# logger_v1.net
KiCad netlist of a schematic drawn in EAGLE
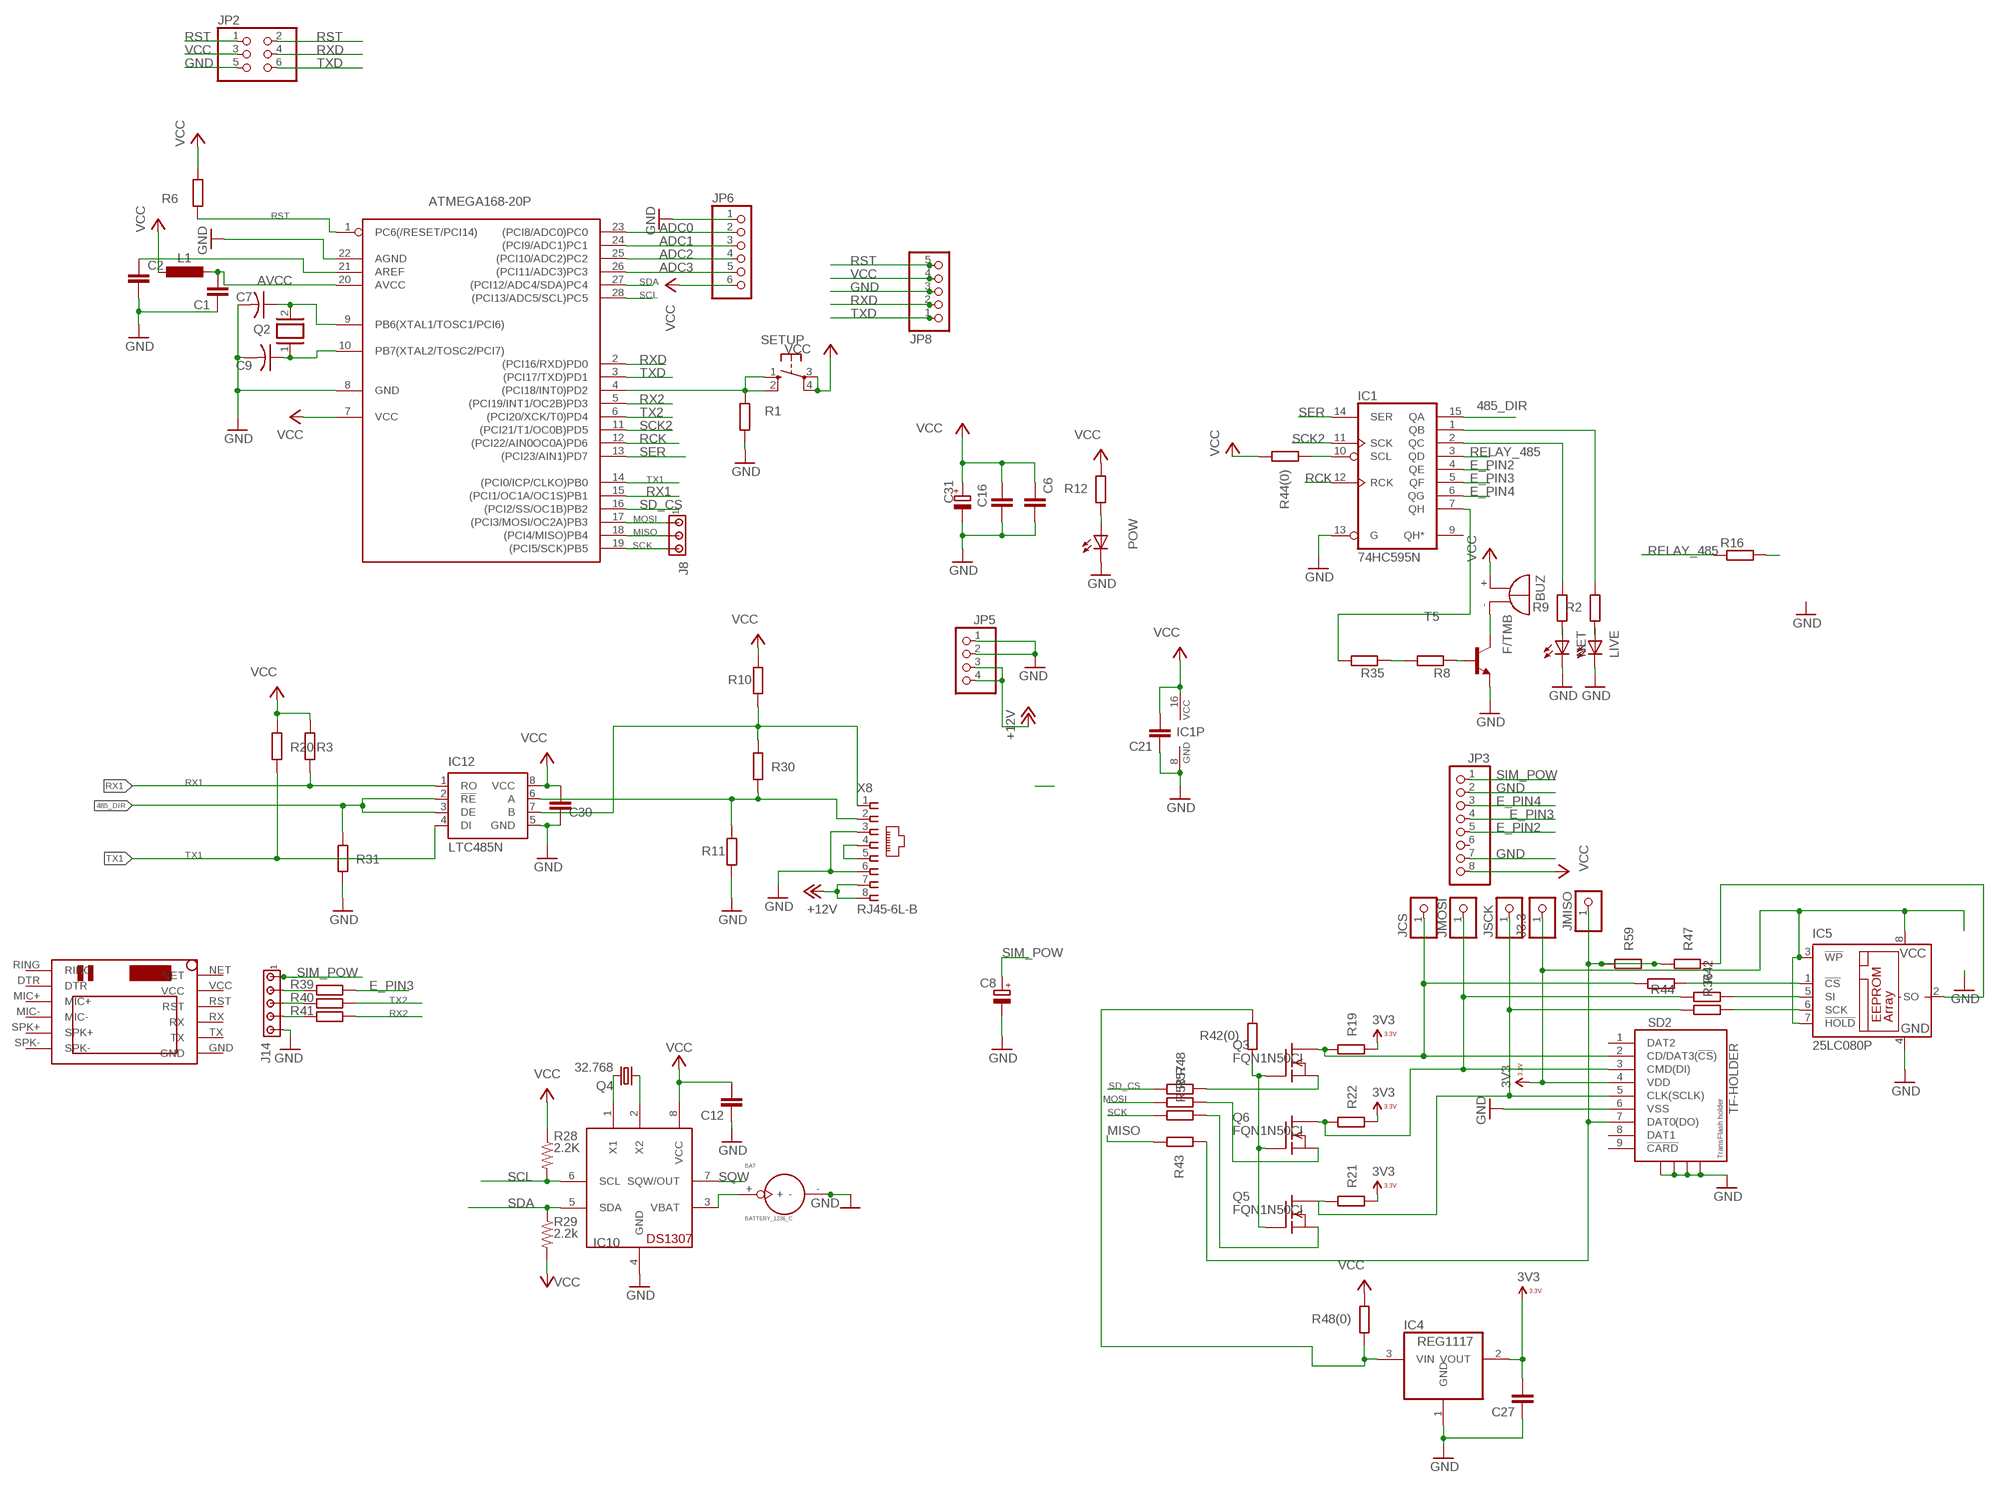
[diagram p0: schematic, sheet 1]
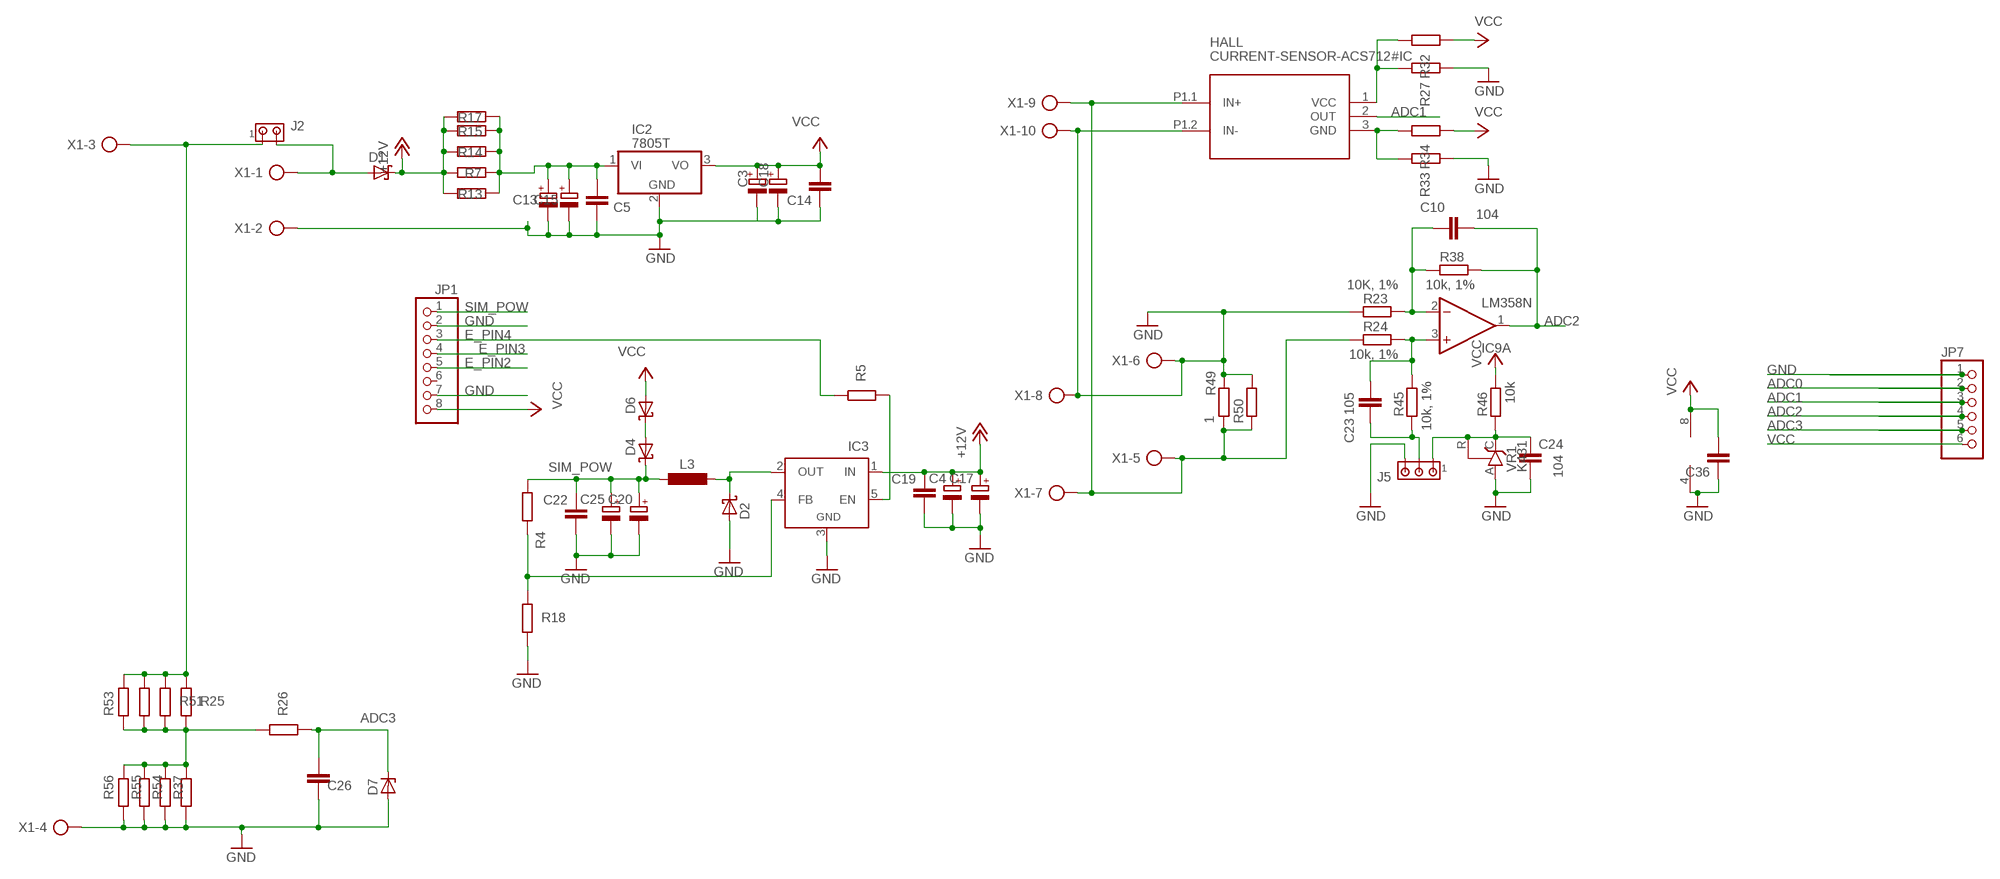
[diagram p1: schematic, sheet 2]

(export (version "E")
  (design (tool "Eeschema 10.0.6"))
  (components
    (comp (ref "C3")
      (value "CPOL-EUTT2D6")
      (footprint "eagle-import:TT2D6")
      (libsource (lib "eagle-import") (part "CPOL-EUTT2D6"))
    )
    (comp (ref "C4")
      (value "CPOL-EUE2.5-6")
      (footprint "eagle-import:E2,5-6")
      (libsource (lib "eagle-import") (part "resistor_CPOL-EUE2.5-6"))
    )
    (comp (ref "C5")
      (value "C-EU050-024X044")
      (footprint "eagle-import:C050-024X044")
      (libsource (lib "eagle-import") (part "C-EU050-024X044"))
    )
    (comp (ref "C10")
      (value "104")
      (footprint "eagle-import:C050-024X044")
      (libsource (lib "eagle-import") (part "C-EU050-024X044"))
    )
    (comp (ref "C13")
      (value "CPOL-EUTT2D6")
      (footprint "eagle-import:TT2D6")
      (libsource (lib "eagle-import") (part "CPOL-EUTT2D6"))
    )
    (comp (ref "C14")
      (value "C-EU050-024X044")
      (footprint "eagle-import:C050-024X044")
      (libsource (lib "eagle-import") (part "C-EU050-024X044"))
    )
    (comp (ref "C15")
      (value "CPOL-EUTT2D6")
      (footprint "eagle-import:TT2D6")
      (libsource (lib "eagle-import") (part "CPOL-EUTT2D6"))
    )
    (comp (ref "C17")
      (value "CPOL-EUE2.5-6")
      (footprint "eagle-import:E2,5-6")
      (libsource (lib "eagle-import") (part "resistor_CPOL-EUE2.5-6"))
    )
    (comp (ref "C18")
      (value "CPOL-EUTT2D6")
      (footprint "eagle-import:TT2D6")
      (libsource (lib "eagle-import") (part "CPOL-EUTT2D6"))
    )
    (comp (ref "C19")
      (value "C-EU050-024X044")
      (footprint "eagle-import:C050-024X044")
      (libsource (lib "eagle-import") (part "resistor_C-EU050-024X044"))
    )
    (comp (ref "C20")
      (value "CPOL-EUE2.5-6")
      (footprint "eagle-import:E2,5-6")
      (libsource (lib "eagle-import") (part "resistor_CPOL-EUE2.5-6"))
    )
    (comp (ref "C22")
      (value "C-EU050-024X044")
      (footprint "eagle-import:C050-024X044")
      (libsource (lib "eagle-import") (part "resistor_C-EU050-024X044"))
    )
    (comp (ref "C23")
      (value "105")
      (footprint "eagle-import:C050-024X044")
      (libsource (lib "eagle-import") (part "C-EU050-024X044"))
    )
    (comp (ref "C24")
      (value "104")
      (footprint "eagle-import:C050-024X044")
      (libsource (lib "eagle-import") (part "C-EU050-024X044"))
    )
    (comp (ref "C25")
      (value "CPOL-EUE2.5-6")
      (footprint "eagle-import:E2,5-6")
      (libsource (lib "eagle-import") (part "resistor_CPOL-EUE2.5-6"))
    )
    (comp (ref "C26")
      (value "C-EU050-024X044")
      (footprint "eagle-import:C050-024X044")
      (libsource (lib "eagle-import") (part "C-EU050-024X044"))
    )
    (comp (ref "C36")
      (value "C-EU050-024X044")
      (footprint "eagle-import:C050-024X044")
      (libsource (lib "eagle-import") (part "C-EU050-024X044"))
    )
    (comp (ref "D1")
      (value "SCHOTTKY-DIODEDO41")
      (footprint "eagle-import:DO41-10")
      (libsource (lib "eagle-import") (part "SCHOTTKY-DIODEDO41"))
    )
    (comp (ref "D2")
      (value "SCHOTTKY-DIODEDO41")
      (footprint "eagle-import:DO41-10")
      (libsource (lib "eagle-import") (part "SCHOTTKY-DIODEDO41"))
    )
    (comp (ref "D4")
      (value "SCHOTTKY-DIODEDO41")
      (footprint "eagle-import:DO41-10")
      (libsource (lib "eagle-import") (part "SCHOTTKY-DIODEDO41"))
    )
    (comp (ref "D6")
      (value "SCHOTTKY-DIODEDO41")
      (footprint "eagle-import:DO41-10")
      (libsource (lib "eagle-import") (part "SCHOTTKY-DIODEDO41"))
    )
    (comp (ref "D7")
      (value "ZENER-DIODEDO35Z10")
      (footprint "eagle-import:DO35Z10")
      (libsource (lib "eagle-import") (part "ZENER-DIODEDO35Z10"))
    )
    (comp (ref "HALL")
      (value "CURRENT-SENSOR-ACS712#IC")
      (footprint "eagle-import:CURRENT-SENSOR-ACS712#IC")
      (libsource (lib "eagle-import") (part "CURRENT-SENSOR-ACS712#IC"))
    )
    (comp (ref "IC2")
      (value "7805T")
      (footprint "eagle-import:TO220H")
      (libsource (lib "eagle-import") (part "78T05"))
    )
    (comp (ref "IC3")
      (value "LM2596TH")
      (footprint "eagle-import:TO220-52")
      (libsource (lib "eagle-import") (part "LM2596TH"))
    )
    (comp (ref "IC9")
      (value "LM358N")
      (footprint "eagle-import:DIL08")
      (libsource (lib "eagle-import") (part "LM358N"))
    )
    (comp (ref "J2")
      (value "MTA02-100")
      (footprint "eagle-import:10X02MTA")
      (libsource (lib "eagle-import") (part "MTA02-100"))
    )
    (comp (ref "J5")
      (value "MTA03-100")
      (footprint "eagle-import:10X03MTA")
      (libsource (lib "eagle-import") (part "MTA03-100"))
    )
    (comp (ref "JP1")
      (value "PINHD-1X8")
      (footprint "eagle-import:1X08")
      (libsource (lib "eagle-import") (part "PINHD-1X8"))
    )
    (comp (ref "JP7")
      (value "PINHD-1X6")
      (footprint "eagle-import:1X06")
      (libsource (lib "eagle-import") (part "PINHD-1X6"))
    )
    (comp (ref "L3")
      (value "L-EU0207/10")
      (footprint "eagle-import:0207_10")
      (libsource (lib "eagle-import") (part "L-EU0207/10"))
    )
    (comp (ref "R4")
      (value "R-EU_0204/7")
      (footprint "eagle-import:0204_7")
      (libsource (lib "eagle-import") (part "R-EU_0204/7"))
    )
    (comp (ref "R5")
      (value "R-EU_0207/12")
      (footprint "eagle-import:0207_12")
      (libsource (lib "eagle-import") (part "R-EU_0207/12"))
    )
    (comp (ref "R7")
      (value "R-EU_0204/7")
      (footprint "eagle-import:0204_7")
      (libsource (lib "eagle-import") (part "R-EU_0204/7"))
    )
    (comp (ref "R13")
      (value "R-EU_0204/7")
      (footprint "eagle-import:0204_7")
      (libsource (lib "eagle-import") (part "R-EU_0204/7"))
    )
    (comp (ref "R14")
      (value "R-EU_0204/7")
      (footprint "eagle-import:0204_7")
      (libsource (lib "eagle-import") (part "R-EU_0204/7"))
    )
    (comp (ref "R15")
      (value "R-EU_0204/7")
      (footprint "eagle-import:0204_7")
      (libsource (lib "eagle-import") (part "R-EU_0204/7"))
    )
    (comp (ref "R17")
      (value "R-EU_0204/7")
      (footprint "eagle-import:0204_7")
      (libsource (lib "eagle-import") (part "R-EU_0204/7"))
    )
    (comp (ref "R18")
      (value "R-EU_0204/7")
      (footprint "eagle-import:0204_7")
      (libsource (lib "eagle-import") (part "R-EU_0204/7"))
    )
    (comp (ref "R23")
      (value "10K, 1%")
      (footprint "eagle-import:0204_7")
      (libsource (lib "eagle-import") (part "R-EU_0204/7"))
    )
    (comp (ref "R24")
      (value "10k, 1%")
      (footprint "eagle-import:0204_7")
      (libsource (lib "eagle-import") (part "R-EU_0204/7"))
    )
    (comp (ref "R25")
      (value "R-EU_0204/7")
      (footprint "eagle-import:0204_7")
      (libsource (lib "eagle-import") (part "R-EU_0204/7"))
    )
    (comp (ref "R26")
      (value "R-EU_0204/7")
      (footprint "eagle-import:0204_7")
      (libsource (lib "eagle-import") (part "R-EU_0204/7"))
    )
    (comp (ref "R27")
      (value "R-EU_0204/7")
      (footprint "eagle-import:0204_7")
      (libsource (lib "eagle-import") (part "R-EU_0204/7"))
    )
    (comp (ref "R32")
      (value "R-EU_0204/7")
      (footprint "eagle-import:0204_7")
      (libsource (lib "eagle-import") (part "R-EU_0204/7"))
    )
    (comp (ref "R33")
      (value "R-EU_0204/7")
      (footprint "eagle-import:0204_7")
      (libsource (lib "eagle-import") (part "R-EU_0204/7"))
    )
    (comp (ref "R34")
      (value "R-EU_0204/7")
      (footprint "eagle-import:0204_7")
      (libsource (lib "eagle-import") (part "R-EU_0204/7"))
    )
    (comp (ref "R37")
      (value "R-EU_0204/7")
      (footprint "eagle-import:0204_7")
      (libsource (lib "eagle-import") (part "R-EU_0204/7"))
    )
    (comp (ref "R38")
      (value "10k, 1%")
      (footprint "eagle-import:0204_7")
      (libsource (lib "eagle-import") (part "R-EU_0204/7"))
    )
    (comp (ref "R45")
      (value "10k, 1%")
      (footprint "eagle-import:0204_7")
      (libsource (lib "eagle-import") (part "R-EU_0204/7"))
    )
    (comp (ref "R46")
      (value "10k")
      (footprint "eagle-import:0207_12")
      (libsource (lib "eagle-import") (part "R-EU_0207/12"))
    )
    (comp (ref "R49")
      (value "1")
      (footprint "eagle-import:MINI_MELF-0207R")
      (libsource (lib "eagle-import") (part "resistor_R-EU_MELF0207R"))
    )
    (comp (ref "R50")
      (value "R-EU_MELF0207R")
      (footprint "eagle-import:MINI_MELF-0207R")
      (libsource (lib "eagle-import") (part "resistor_R-EU_MELF0207R"))
    )
    (comp (ref "R51")
      (value "R-EU_0204/7")
      (footprint "eagle-import:0204_7")
      (libsource (lib "eagle-import") (part "R-EU_0204/7"))
    )
    (comp (ref "R52")
      (value "R-EU_0204/7")
      (footprint "eagle-import:0204_7")
      (libsource (lib "eagle-import") (part "R-EU_0204/7"))
    )
    (comp (ref "R53")
      (value "R-EU_0204/7")
      (footprint "eagle-import:0204_7")
      (libsource (lib "eagle-import") (part "R-EU_0204/7"))
    )
    (comp (ref "R54")
      (value "R-EU_0204/7")
      (footprint "eagle-import:0204_7")
      (libsource (lib "eagle-import") (part "R-EU_0204/7"))
    )
    (comp (ref "R55")
      (value "R-EU_0204/7")
      (footprint "eagle-import:0204_7")
      (libsource (lib "eagle-import") (part "R-EU_0204/7"))
    )
    (comp (ref "R56")
      (value "R-EU_0204/7")
      (footprint "eagle-import:0204_7")
      (libsource (lib "eagle-import") (part "R-EU_0204/7"))
    )
    (comp (ref "VR1")
      (value "K431")
      (footprint "eagle-import:TO92-CLP")
      (libsource (lib "eagle-import") (part "TL431CLP"))
    )
    (comp (ref "X1")
      (value "AK500/10")
      (footprint "eagle-import:AK500_10")
      (libsource (lib "eagle-import") (part "AK500/10"))
    )
    (comp (ref "BAT")
      (value "BATTERY_1236_C")
      (footprint "eagle-import:BATTERY_1236_C")
      (libsource (lib "eagle-import") (part "BATTERY_1236_C"))
    )
    (comp (ref "BUZ")
      (value "F/TMB")
      (footprint "eagle-import:F_TMB")
      (libsource (lib "eagle-import") (part "F/TMB"))
    )
    (comp (ref "C1")
      (value "C-EU050-024X044")
      (footprint "eagle-import:C050-024X044")
      (libsource (lib "eagle-import") (part "C-EU050-024X044"))
    )
    (comp (ref "C2")
      (value "C-EU025-025X050")
      (footprint "eagle-import:C025-025X050")
      (libsource (lib "eagle-import") (part "C-EU025-025X050"))
    )
    (comp (ref "C6")
      (value "C-EU025-025X050")
      (footprint "eagle-import:C025-025X050")
      (libsource (lib "eagle-import") (part "C-EU025-025X050"))
    )
    (comp (ref "C7")
      (value "C-US050-024X044")
      (footprint "eagle-import:C050-024X044")
      (libsource (lib "eagle-import") (part "C-US050-024X044"))
    )
    (comp (ref "C8")
      (value "CPOL-EUE2.5-6")
      (footprint "eagle-import:E2,5-6")
      (libsource (lib "eagle-import") (part "resistor_CPOL-EUE2.5-6"))
    )
    (comp (ref "C9")
      (value "C-US050-024X044")
      (footprint "eagle-import:C050-024X044")
      (libsource (lib "eagle-import") (part "C-US050-024X044"))
    )
    (comp (ref "C12")
      (value "C-EU075-032X103")
      (footprint "eagle-import:C075-032X103")
      (libsource (lib "eagle-import") (part "C-EU075-032X103"))
    )
    (comp (ref "C16")
      (value "C-EU050-024X044")
      (footprint "eagle-import:C050-024X044")
      (libsource (lib "eagle-import") (part "C-EU050-024X044"))
    )
    (comp (ref "C21")
      (value "C-EU050-024X044")
      (footprint "eagle-import:C050-024X044")
      (libsource (lib "eagle-import") (part "C-EU050-024X044"))
    )
    (comp (ref "C27")
      (value "C-EU050-024X044")
      (footprint "eagle-import:C050-024X044")
      (libsource (lib "eagle-import") (part "C-EU050-024X044"))
    )
    (comp (ref "C30")
      (value "C-EU050-024X044")
      (footprint "eagle-import:C050-024X044")
      (libsource (lib "eagle-import") (part "C-EU050-024X044"))
    )
    (comp (ref "C31")
      (value "CPOL-EUTT2D6")
      (footprint "eagle-import:TT2D6")
      (libsource (lib "eagle-import") (part "CPOL-EUTT2D6"))
    )
    (comp (ref "IC1")
      (value "74HC595N")
      (footprint "eagle-import:DIL16")
      (libsource (lib "eagle-import") (part "74595NHC"))
    )
    (comp (ref "IC4")
      (value "REG1117")
      (footprint "eagle-import:SOT223")
      (libsource (lib "eagle-import") (part "REG1117"))
    )
    (comp (ref "IC5")
      (value "25LC080P")
      (footprint "eagle-import:DIL8")
      (fields (field (name "MF") "MICROCHIP") (field (name "MPN") "25LC080/P"))
      (libsource (lib "eagle-import") (part "25PLC080"))
    )
    (comp (ref "IC7")
      (value "ATMEGA168-20P")
      (footprint "eagle-import:DIL28-3")
      (libsource (lib "eagle-import") (part "ATMEGA168P-20"))
    )
    (comp (ref "IC10")
      (value "DS1307")
      (footprint "eagle-import:DIL08")
      (libsource (lib "eagle-import") (part "DS1307"))
    )
    (comp (ref "IC12")
      (value "LTC485N")
      (footprint "eagle-import:DIL08")
      (libsource (lib "eagle-import") (part "LTC485N"))
    )
    (comp (ref "J3.3")
      (value "PINHD-1X1")
      (footprint "eagle-import:1X01")
      (libsource (lib "eagle-import") (part "PINHD-1X1"))
    )
    (comp (ref "J8")
      (value "MTA03-100")
      (footprint "eagle-import:10X03MTA")
      (libsource (lib "eagle-import") (part "MTA03-100"))
    )
    (comp (ref "J14")
      (value "MTA05-100")
      (footprint "eagle-import:10X05MTA")
      (libsource (lib "eagle-import") (part "MTA05-100"))
    )
    (comp (ref "JCS")
      (value "PINHD-1X1")
      (footprint "eagle-import:1X01")
      (libsource (lib "eagle-import") (part "PINHD-1X1"))
    )
    (comp (ref "JMISO")
      (value "PINHD-1X1")
      (footprint "eagle-import:1X01")
      (libsource (lib "eagle-import") (part "PINHD-1X1"))
    )
    (comp (ref "JMOSI")
      (value "PINHD-1X1")
      (footprint "eagle-import:1X01")
      (libsource (lib "eagle-import") (part "PINHD-1X1"))
    )
    (comp (ref "JP2")
      (value "PINHD-2X3")
      (footprint "eagle-import:2X03")
      (libsource (lib "eagle-import") (part "PINHD-2X3"))
    )
    (comp (ref "JP3")
      (value "PINHD-1X8")
      (footprint "eagle-import:1X08")
      (libsource (lib "eagle-import") (part "PINHD-1X8"))
    )
    (comp (ref "JP5")
      (value "PINHD-1X4")
      (footprint "eagle-import:1X04")
      (libsource (lib "eagle-import") (part "PINHD-1X4"))
    )
    (comp (ref "JP6")
      (value "PINHD-1X6")
      (footprint "eagle-import:1X06")
      (libsource (lib "eagle-import") (part "PINHD-1X6"))
    )
    (comp (ref "JP8")
      (value "PINHD-1X5/90")
      (footprint "eagle-import:1X05_90")
      (libsource (lib "eagle-import") (part "PINHD-1X5/90"))
    )
    (comp (ref "JSCK")
      (value "PINHD-1X1")
      (footprint "eagle-import:1X01")
      (libsource (lib "eagle-import") (part "PINHD-1X1"))
    )
    (comp (ref "L1")
      (value "L-EU0207/15")
      (footprint "eagle-import:0207_15")
      (libsource (lib "eagle-import") (part "L-EU0207/15"))
    )
    (comp (ref "LIVE")
      (value "LED3MM")
      (footprint "eagle-import:LED3MM")
      (libsource (lib "eagle-import") (part "LED3MM"))
    )
    (comp (ref "NET")
      (value "LED3MM")
      (footprint "eagle-import:LED3MM")
      (libsource (lib "eagle-import") (part "LED3MM"))
    )
    (comp (ref "POW")
      (value "LED3MM")
      (footprint "eagle-import:LED3MM")
      (libsource (lib "eagle-import") (part "LED3MM"))
    )
    (comp (ref "Q2")
      (value "XTAL/S")
      (footprint "eagle-import:QS")
      (libsource (lib "eagle-import") (part "XTAL/S"))
    )
    (comp (ref "Q3")
      (value "FQN1N50CI")
      (footprint "eagle-import:TO92-INLINE")
      (libsource (lib "eagle-import") (part "FQN1N50CI"))
    )
    (comp (ref "Q4")
      (value "32.768")
      (footprint "eagle-import:TC38H")
      (libsource (lib "eagle-import") (part "CRYTALTC38H"))
    )
    (comp (ref "Q5")
      (value "FQN1N50CI")
      (footprint "eagle-import:TO92-INLINE")
      (libsource (lib "eagle-import") (part "FQN1N50CI"))
    )
    (comp (ref "Q6")
      (value "FQN1N50CI")
      (footprint "eagle-import:TO92-INLINE")
      (libsource (lib "eagle-import") (part "FQN1N50CI"))
    )
    (comp (ref "R1")
      (value "R-EU_0204/7")
      (footprint "eagle-import:0204_7")
      (libsource (lib "eagle-import") (part "R-EU_0204/7"))
    )
    (comp (ref "R2")
      (value "R-EU_0207/12")
      (footprint "eagle-import:0207_12")
      (libsource (lib "eagle-import") (part "R-EU_0207/12"))
    )
    (comp (ref "R3")
      (value "R-EU_0204/7")
      (footprint "eagle-import:0204_7")
      (libsource (lib "eagle-import") (part "R-EU_0204/7"))
    )
    (comp (ref "R6")
      (value "R-EU_0204/7")
      (footprint "eagle-import:0204_7")
      (libsource (lib "eagle-import") (part "R-EU_0204/7"))
    )
    (comp (ref "R8")
      (value "R-EU_0207/10")
      (footprint "eagle-import:0207_10")
      (libsource (lib "eagle-import") (part "R-EU_0207/10"))
    )
    (comp (ref "R9")
      (value "R-EU_0207/12")
      (footprint "eagle-import:0207_12")
      (libsource (lib "eagle-import") (part "R-EU_0207/12"))
    )
    (comp (ref "R10")
      (value "R-EU_0204/7")
      (footprint "eagle-import:0204_7")
      (libsource (lib "eagle-import") (part "R-EU_0204/7"))
    )
    (comp (ref "R11")
      (value "R-EU_0204/7")
      (footprint "eagle-import:0204_7")
      (libsource (lib "eagle-import") (part "R-EU_0204/7"))
    )
    (comp (ref "R12")
      (value "R-EU_0204/7")
      (footprint "eagle-import:0204_7")
      (libsource (lib "eagle-import") (part "R-EU_0204/7"))
    )
    (comp (ref "R16")
      (value "R-EU_0207/10")
      (footprint "eagle-import:0207_10")
      (libsource (lib "eagle-import") (part "resistor_R-EU_0207/10"))
    )
    (comp (ref "R19")
      (value "R-EU_0204/7")
      (footprint "eagle-import:0204_7")
      (libsource (lib "eagle-import") (part "R-EU_0204/7"))
    )
    (comp (ref "R20")
      (value "R-EU_0204/7")
      (footprint "eagle-import:0204_7")
      (libsource (lib "eagle-import") (part "R-EU_0204/7"))
    )
    (comp (ref "R21")
      (value "R-EU_0204/7")
      (footprint "eagle-import:0204_7")
      (libsource (lib "eagle-import") (part "R-EU_0204/7"))
    )
    (comp (ref "R22")
      (value "R-EU_0204/7")
      (footprint "eagle-import:0204_7")
      (libsource (lib "eagle-import") (part "R-EU_0204/7"))
    )
    (comp (ref "R28")
      (value "2.2K")
      (footprint "eagle-import:0204_7")
      (libsource (lib "eagle-import") (part "R-US_0204/7"))
    )
    (comp (ref "R29")
      (value "2.2k")
      (footprint "eagle-import:0204_7")
      (libsource (lib "eagle-import") (part "R-US_0204/7"))
    )
    (comp (ref "R30")
      (value "R-EU_0204/7")
      (footprint "eagle-import:0204_7")
      (libsource (lib "eagle-import") (part "R-EU_0204/7"))
    )
    (comp (ref "R31")
      (value "R-EU_0204/7")
      (footprint "eagle-import:0204_7")
      (libsource (lib "eagle-import") (part "R-EU_0204/7"))
    )
    (comp (ref "R35")
      (value "R-EU_0204/7")
      (footprint "eagle-import:0204_7")
      (libsource (lib "eagle-import") (part "R-EU_0204/7"))
    )
    (comp (ref "R36")
      (value "R-EU_0207/10")
      (footprint "eagle-import:0207_10")
      (libsource (lib "eagle-import") (part "R-EU_0207/10"))
    )
    (comp (ref "R39")
      (value "R-EU_0207/10")
      (footprint "eagle-import:0207_10")
      (libsource (lib "eagle-import") (part "R-EU_0207/10"))
    )
    (comp (ref "R40")
      (value "R-EU_0207/12")
      (footprint "eagle-import:0207_12")
      (libsource (lib "eagle-import") (part "R-EU_0207/12"))
    )
    (comp (ref "R41")
      (value "R-EU_0207/12")
      (footprint "eagle-import:0207_12")
      (libsource (lib "eagle-import") (part "R-EU_0207/12"))
    )
    (comp (ref "R42")
      (value "R-EU_0207/10")
      (footprint "eagle-import:0207_10")
      (libsource (lib "eagle-import") (part "R-EU_0207/10"))
    )
    (comp (ref "R42(0)")
      (value "R-EU_0207/10")
      (footprint "eagle-import:0207_10")
      (libsource (lib "eagle-import") (part "R-EU_0207/10"))
    )
    (comp (ref "R43")
      (value "R-EU_0204/7")
      (footprint "eagle-import:0204_7")
      (libsource (lib "eagle-import") (part "R-EU_0204/7"))
    )
    (comp (ref "R44")
      (value "R-EU_0207/10")
      (footprint "eagle-import:0207_10")
      (libsource (lib "eagle-import") (part "R-EU_0207/10"))
    )
    (comp (ref "R44(0)")
      (value "R-EU_0207/10")
      (footprint "eagle-import:0207_10")
      (libsource (lib "eagle-import") (part "R-EU_0207/10"))
    )
    (comp (ref "R47")
      (value "R-EU_0207/10")
      (footprint "eagle-import:0207_10")
      (libsource (lib "eagle-import") (part "R-EU_0207/10"))
    )
    (comp (ref "R48")
      (value "R-EU_0204/7")
      (footprint "eagle-import:0204_7")
      (libsource (lib "eagle-import") (part "R-EU_0204/7"))
    )
    (comp (ref "R48(0)")
      (value "R-EU_0207/10")
      (footprint "eagle-import:0207_10")
      (libsource (lib "eagle-import") (part "R-EU_0207/10"))
    )
    (comp (ref "R57")
      (value "R-EU_0204/7")
      (footprint "eagle-import:0204_7")
      (libsource (lib "eagle-import") (part "R-EU_0204/7"))
    )
    (comp (ref "R58")
      (value "R-EU_0204/7")
      (footprint "eagle-import:0204_7")
      (libsource (lib "eagle-import") (part "R-EU_0204/7"))
    )
    (comp (ref "R59")
      (value "R-EU_0204/7")
      (footprint "eagle-import:0204_7")
      (libsource (lib "eagle-import") (part "R-EU_0204/7"))
    )
    (comp (ref "SD2")
      (value "TF-HOLDER")
      (footprint "eagle-import:TF-PULL")
      (libsource (lib "eagle-import") (part "TF-HOLDER"))
    )
    (comp (ref "SETUP")
      (value "10-XX")
      (footprint "eagle-import:B3F-10XX")
      (fields (field (name "MPN") "B3F-1000"))
      (libsource (lib "eagle-import") (part "10-XX"))
    )
    (comp (ref "T5")
      (value "BC547A-NPN-TO92-CBE")
      (footprint "eagle-import:TO92-CBE")
      (libsource (lib "eagle-import") (part "-NPN-TO92-CBEBC547A"))
    )
    (comp (ref "U$1")
      (value "SIM800LMODULE")
      (footprint "eagle-import:SIM800LMODULE")
      (libsource (lib "eagle-import") (part "SIM800LMODULE"))
    )
    (comp (ref "X8")
      (value "RJ45-6L-B")
      (footprint "eagle-import:RJ45-NO-SHIELD")
      (libsource (lib "eagle-import") (part "RJ45-6L-B"))
    )
  )
  (nets
    (net (code "1") (name "+12V") (class "Default")
      (node (ref "C17") (pin "+") (pinfunction "+_+") (pintype "passive"))
      (node (ref "C19") (pin "1") (pinfunction "1_1") (pintype "passive"))
      (node (ref "C4") (pin "+") (pinfunction "+_+") (pintype "passive"))
      (node (ref "D1") (pin "C") (pinfunction "C_C") (pintype "passive"))
      (node (ref "IC3") (pin "1") (pinfunction "IN_1") (pintype "input"))
      (node (ref "JP5") (pin "3") (pinfunction "3_3") (pintype "passive"))
      (node (ref "JP5") (pin "4") (pinfunction "4_4") (pintype "passive"))
      (node (ref "R13") (pin "2") (pinfunction "2_2") (pintype "passive"))
      (node (ref "R14") (pin "2") (pinfunction "2_2") (pintype "passive"))
      (node (ref "R15") (pin "2") (pinfunction "2_2") (pintype "passive"))
      (node (ref "R17") (pin "2") (pinfunction "2_2") (pintype "passive"))
      (node (ref "R7") (pin "2") (pinfunction "2_2") (pintype "passive"))
      (node (ref "X8") (pin "7") (pinfunction "7_7") (pintype "passive"))
      (node (ref "X8") (pin "8") (pinfunction "8_8") (pintype "passive"))
    )
    (net (code "2") (name "3V3") (class "Default")
      (node (ref "C27") (pin "2") (pinfunction "2_2") (pintype "passive"))
      (node (ref "IC4") (pin "2") (pinfunction "VOUT_2") (pintype "output"))
      (node (ref "IC5") (pin "3") (pinfunction "~{WP}_3") (pintype "input"))
      (node (ref "IC5") (pin "7") (pinfunction "~{HOLD}_7") (pintype "input"))
      (node (ref "IC5") (pin "8") (pinfunction "VCC_8") (pintype "power_in"))
      (node (ref "J3.3") (pin "1") (pinfunction "1_1") (pintype "passive"))
      (node (ref "R19") (pin "2") (pinfunction "2_2") (pintype "passive"))
      (node (ref "R21") (pin "2") (pinfunction "2_2") (pintype "passive"))
      (node (ref "R22") (pin "2") (pinfunction "2_2") (pintype "passive"))
      (node (ref "SD2") (pin "4") (pinfunction "VDD_4") (pintype "power_in"))
    )
    (net (code "3") (name "485_DIR") (class "Default")
      (node (ref "IC1") (pin "15") (pinfunction "QA_15") (pintype "tri_state"))
      (node (ref "IC12") (pin "2") (pinfunction "~{RE}_2") (pintype "input"))
      (node (ref "IC12") (pin "3") (pinfunction "DE_3") (pintype "input"))
      (node (ref "R31") (pin "1") (pinfunction "1_1") (pintype "passive"))
    )
    (net (code "4") (name "ADC0") (class "Default")
      (node (ref "IC7") (pin "23") (pinfunction "(PCI8/ADC0)PC0_23") (pintype "bidirectional"))
      (node (ref "JP6") (pin "2") (pinfunction "2_2") (pintype "passive"))
      (node (ref "JP7") (pin "2") (pinfunction "2_2") (pintype "passive"))
    )
    (net (code "5") (name "ADC1") (class "Default")
      (node (ref "HALL") (pin "2") (pinfunction "OUT_2") (pintype "output"))
      (node (ref "IC7") (pin "24") (pinfunction "(PCI9/ADC1)PC1_24") (pintype "bidirectional"))
      (node (ref "JP6") (pin "3") (pinfunction "3_3") (pintype "passive"))
      (node (ref "JP7") (pin "3") (pinfunction "3_3") (pintype "passive"))
    )
    (net (code "6") (name "ADC2") (class "Default")
      (node (ref "C10") (pin "1") (pinfunction "1_1") (pintype "passive"))
      (node (ref "IC7") (pin "25") (pinfunction "(PCI10/ADC2)PC2_25") (pintype "bidirectional"))
      (node (ref "IC9") (pin "1") (pinfunction "OUT_1") (pintype "output"))
      (node (ref "JP6") (pin "4") (pinfunction "4_4") (pintype "passive"))
      (node (ref "JP7") (pin "4") (pinfunction "4_4") (pintype "passive"))
      (node (ref "R38") (pin "1") (pinfunction "1_1") (pintype "passive"))
    )
    (net (code "7") (name "ADC3") (class "Default")
      (node (ref "C26") (pin "2") (pinfunction "2_2") (pintype "passive"))
      (node (ref "D7") (pin "C") (pinfunction "C_C") (pintype "passive"))
      (node (ref "IC7") (pin "26") (pinfunction "(PCI11/ADC3)PC3_26") (pintype "bidirectional"))
      (node (ref "JP6") (pin "5") (pinfunction "5_5") (pintype "passive"))
      (node (ref "JP7") (pin "5") (pinfunction "5_5") (pintype "passive"))
      (node (ref "R26") (pin "1") (pinfunction "1_1") (pintype "passive"))
    )
    (net (code "8") (name "AVCC") (class "Default")
      (node (ref "C1") (pin "2") (pinfunction "2_2") (pintype "passive"))
      (node (ref "IC7") (pin "20") (pinfunction "AVCC_20") (pintype "bidirectional"))
      (node (ref "L1") (pin "2") (pinfunction "2_2") (pintype "passive"))
    )
    (net (code "9") (name "E_PIN2") (class "Default")
      (node (ref "IC1") (pin "4") (pinfunction "QE_4") (pintype "tri_state"))
      (node (ref "JP1") (pin "5") (pinfunction "5_5") (pintype "passive"))
      (node (ref "JP3") (pin "5") (pinfunction "5_5") (pintype "passive"))
    )
    (net (code "10") (name "E_PIN3") (class "Default")
      (node (ref "IC1") (pin "5") (pinfunction "QF_5") (pintype "tri_state"))
      (node (ref "JP1") (pin "4") (pinfunction "4_4") (pintype "passive"))
      (node (ref "JP3") (pin "4") (pinfunction "4_4") (pintype "passive"))
      (node (ref "R39") (pin "1") (pinfunction "1_1") (pintype "passive"))
    )
    (net (code "11") (name "E_PIN4") (class "Default")
      (node (ref "IC1") (pin "6") (pinfunction "QG_6") (pintype "tri_state"))
      (node (ref "JP1") (pin "3") (pinfunction "3_3") (pintype "passive"))
      (node (ref "JP3") (pin "3") (pinfunction "3_3") (pintype "passive"))
      (node (ref "R5") (pin "2") (pinfunction "2_2") (pintype "passive"))
    )
    (net (code "12") (name "GND") (class "Default")
      (node (ref "BAT") (pin "-") (pinfunction "-_-") (pintype "bidirectional"))
      (node (ref "C1") (pin "1") (pinfunction "1_1") (pintype "passive"))
      (node (ref "C12") (pin "1") (pinfunction "1_1") (pintype "passive"))
      (node (ref "C13") (pin "-") (pinfunction "-_-") (pintype "passive"))
      (node (ref "C14") (pin "1") (pinfunction "1_1") (pintype "passive"))
      (node (ref "C15") (pin "-") (pinfunction "-_-") (pintype "passive"))
      (node (ref "C16") (pin "1") (pinfunction "1_1") (pintype "passive"))
      (node (ref "C17") (pin "-") (pinfunction "-_-") (pintype "passive"))
      (node (ref "C18") (pin "-") (pinfunction "-_-") (pintype "passive"))
      (node (ref "C19") (pin "2") (pinfunction "2_2") (pintype "passive"))
      (node (ref "C2") (pin "1") (pinfunction "1_1") (pintype "passive"))
      (node (ref "C20") (pin "-") (pinfunction "-_-") (pintype "passive"))
      (node (ref "C21") (pin "1") (pinfunction "1_1") (pintype "passive"))
      (node (ref "C22") (pin "2") (pinfunction "2_2") (pintype "passive"))
      (node (ref "C24") (pin "2") (pinfunction "2_2") (pintype "passive"))
      (node (ref "C25") (pin "-") (pinfunction "-_-") (pintype "passive"))
      (node (ref "C26") (pin "1") (pinfunction "1_1") (pintype "passive"))
      (node (ref "C27") (pin "1") (pinfunction "1_1") (pintype "passive"))
      (node (ref "C3") (pin "-") (pinfunction "-_-") (pintype "passive"))
      (node (ref "C30") (pin "1") (pinfunction "1_1") (pintype "passive"))
      (node (ref "C31") (pin "-") (pinfunction "-_-") (pintype "passive"))
      (node (ref "C36") (pin "1") (pinfunction "1_1") (pintype "passive"))
      (node (ref "C4") (pin "-") (pinfunction "-_-") (pintype "passive"))
      (node (ref "C5") (pin "1") (pinfunction "1_1") (pintype "passive"))
      (node (ref "C6") (pin "1") (pinfunction "1_1") (pintype "passive"))
      (node (ref "C7") (pin "2") (pinfunction "2_2") (pintype "passive"))
      (node (ref "C8") (pin "-") (pinfunction "-_-") (pintype "passive"))
      (node (ref "C9") (pin "2") (pinfunction "2_2") (pintype "passive"))
      (node (ref "D2") (pin "A") (pinfunction "A_A") (pintype "passive"))
      (node (ref "D7") (pin "A") (pinfunction "A_A") (pintype "passive"))
      (node (ref "HALL") (pin "P1.2") (pinfunction "IN-_P1.2") (pintype "bidirectional"))
      (node (ref "IC1") (pin "13") (pinfunction "G_13") (pintype "input"))
      (node (ref "IC1") (pin "8") (pinfunction "GND_8") (pintype "power_in"))
      (node (ref "IC10") (pin "4") (pinfunction "GND_4") (pintype "power_in"))
      (node (ref "IC12") (pin "5") (pinfunction "GND_5") (pintype "input"))
      (node (ref "IC2") (pin "2") (pinfunction "GND_2") (pintype "passive"))
      (node (ref "IC3") (pin "3") (pinfunction "GND_3") (pintype "power_in"))
      (node (ref "IC4") (pin "1") (pinfunction "GND_1") (pintype "power_in"))
      (node (ref "IC5") (pin "4") (pinfunction "GND_4") (pintype "power_in"))
      (node (ref "IC7") (pin "22") (pinfunction "AGND_22") (pintype "bidirectional"))
      (node (ref "IC7") (pin "8") (pinfunction "GND_8") (pintype "bidirectional"))
      (node (ref "IC9") (pin "4") (pinfunction "V-_4") (pintype "power_in"))
      (node (ref "J14") (pin "5") (pinfunction "5_5") (pintype "passive"))
      (node (ref "J5") (pin "3") (pinfunction "3_3") (pintype "passive"))
      (node (ref "JP1") (pin "2") (pinfunction "2_2") (pintype "passive"))
      (node (ref "JP1") (pin "7") (pinfunction "7_7") (pintype "passive"))
      (node (ref "JP2") (pin "5") (pinfunction "5_5") (pintype "passive"))
      (node (ref "JP3") (pin "2") (pinfunction "2_2") (pintype "passive"))
      (node (ref "JP3") (pin "7") (pinfunction "7_7") (pintype "passive"))
      (node (ref "JP5") (pin "1") (pinfunction "1_1") (pintype "passive"))
      (node (ref "JP5") (pin "2") (pinfunction "2_2") (pintype "passive"))
      (node (ref "JP6") (pin "1") (pinfunction "1_1") (pintype "passive"))
      (node (ref "JP7") (pin "1") (pinfunction "1_1") (pintype "passive"))
      (node (ref "JP8") (pin "3") (pinfunction "3_3") (pintype "passive"))
      (node (ref "LIVE") (pin "K") (pinfunction "C_K") (pintype "passive"))
      (node (ref "NET") (pin "K") (pinfunction "C_K") (pintype "passive"))
      (node (ref "POW") (pin "K") (pinfunction "C_K") (pintype "passive"))
      (node (ref "R1") (pin "2") (pinfunction "2_2") (pintype "passive"))
      (node (ref "R11") (pin "1") (pinfunction "1_1") (pintype "passive"))
      (node (ref "R18") (pin "1") (pinfunction "1_1") (pintype "passive"))
      (node (ref "R23") (pin "2") (pinfunction "2_2") (pintype "passive"))
      (node (ref "R27") (pin "1") (pinfunction "1_1") (pintype "passive"))
      (node (ref "R31") (pin "2") (pinfunction "2_2") (pintype "passive"))
      (node (ref "R33") (pin "1") (pinfunction "1_1") (pintype "passive"))
      (node (ref "R37") (pin "1") (pinfunction "1_1") (pintype "passive"))
      (node (ref "R49") (pin "2") (pinfunction "2_2") (pintype "passive"))
      (node (ref "R50") (pin "2") (pinfunction "2_2") (pintype "passive"))
      (node (ref "R54") (pin "1") (pinfunction "1_1") (pintype "passive"))
      (node (ref "R55") (pin "1") (pinfunction "1_1") (pintype "passive"))
      (node (ref "R56") (pin "1") (pinfunction "1_1") (pintype "passive"))
      (node (ref "SD2") (pin "6") (pinfunction "VSS_6") (pintype "power_in"))
      (node (ref "SD2") (pin "S1") (pinfunction "S1_S1") (pintype "passive"))
      (node (ref "SD2") (pin "S2") (pinfunction "S2_S2") (pintype "passive"))
      (node (ref "SD2") (pin "S3") (pinfunction "S3_S3") (pintype "passive"))
      (node (ref "SD2") (pin "S4") (pinfunction "S4_S4") (pintype "passive"))
      (node (ref "T5") (pin "E") (pinfunction "E_E") (pintype "passive"))
      (node (ref "VR1") (pin "A") (pinfunction "A_A") (pintype "passive"))
      (node (ref "X1") (pin "10") (pinfunction "KL_10") (pintype "passive"))
      (node (ref "X1") (pin "2") (pinfunction "KL_2") (pintype "passive"))
      (node (ref "X1") (pin "4") (pinfunction "KL_4") (pintype "passive"))
      (node (ref "X1") (pin "6") (pinfunction "KL_6") (pintype "passive"))
      (node (ref "X1") (pin "8") (pinfunction "KL_8") (pintype "passive"))
      (node (ref "X8") (pin "3") (pinfunction "3_3") (pintype "passive"))
      (node (ref "X8") (pin "6") (pinfunction "6_6") (pintype "passive"))
    )
    (net (code "13") (name "MISO") (class "Default")
      (node (ref "IC7") (pin "18") (pinfunction "(PCI4/MISO)PB4_18") (pintype "bidirectional"))
      (node (ref "J8") (pin "2") (pinfunction "2_2") (pintype "passive"))
      (node (ref "R43") (pin "2") (pinfunction "2_2") (pintype "passive"))
    )
    (net (code "14") (name "MOSI") (class "Default")
      (node (ref "IC7") (pin "17") (pinfunction "(PCI3/MOSI/OC2A)PB3_17") (pintype "bidirectional"))
      (node (ref "J8") (pin "1") (pinfunction "1_1") (pintype "passive"))
      (node (ref "Q6") (pin "3") (pinfunction "S_3") (pintype "passive"))
      (node (ref "R57") (pin "1") (pinfunction "1_1") (pintype "passive"))
      (node (ref "R57") (pin "2") (pinfunction "2_2") (pintype "passive"))
    )
    (net (code "15") (name "Net-(BUZ-Pad-)") (class "Default")
      (node (ref "BUZ") (pin "-") (pinfunction "-_-") (pintype "passive"))
      (node (ref "T5") (pin "C") (pinfunction "C_C") (pintype "passive"))
    )
    (net (code "16") (name "Net-(C23-Pad2)") (class "Default")
      (node (ref "C23") (pin "2") (pinfunction "2_2") (pintype "passive"))
      (node (ref "J5") (pin "2") (pinfunction "2_2") (pintype "passive"))
      (node (ref "R45") (pin "2") (pinfunction "2_2") (pintype "passive"))
    )
    (net (code "17") (name "Net-(C24-Pad1)") (class "Default")
      (node (ref "C24") (pin "1") (pinfunction "1_1") (pintype "passive"))
      (node (ref "J5") (pin "1") (pinfunction "1_1") (pintype "passive"))
      (node (ref "R46") (pin "2") (pinfunction "2_2") (pintype "passive"))
      (node (ref "VR1") (pin "C") (pinfunction "C_C") (pintype "passive"))
      (node (ref "VR1") (pin "R") (pinfunction "R_R") (pintype "passive"))
    )
    (net (code "18") (name "Net-(D4-PadA)") (class "Default")
      (node (ref "D4") (pin "A") (pinfunction "A_A") (pintype "passive"))
      (node (ref "D6") (pin "C") (pinfunction "C_C") (pintype "passive"))
    )
    (net (code "19") (name "Net-(HALL-GND)") (class "Default")
      (node (ref "HALL") (pin "3") (pinfunction "GND_3") (pintype "power_in"))
      (node (ref "R33") (pin "2") (pinfunction "2_2") (pintype "passive"))
      (node (ref "R34") (pin "2") (pinfunction "2_2") (pintype "passive"))
    )
    (net (code "20") (name "Net-(HALL-IN+)") (class "Default")
      (node (ref "HALL") (pin "P1.1") (pinfunction "IN+_P1.1") (pintype "bidirectional"))
      (node (ref "R24") (pin "2") (pinfunction "2_2") (pintype "passive"))
      (node (ref "R49") (pin "1") (pinfunction "1_1") (pintype "passive"))
      (node (ref "R50") (pin "1") (pinfunction "1_1") (pintype "passive"))
      (node (ref "X1") (pin "5") (pinfunction "KL_5") (pintype "passive"))
      (node (ref "X1") (pin "7") (pinfunction "KL_7") (pintype "passive"))
      (node (ref "X1") (pin "9") (pinfunction "KL_9") (pintype "passive"))
    )
    (net (code "21") (name "Net-(HALL-VCC)") (class "Default")
      (node (ref "HALL") (pin "1") (pinfunction "VCC_1") (pintype "power_in"))
      (node (ref "R27") (pin "2") (pinfunction "2_2") (pintype "passive"))
      (node (ref "R32") (pin "2") (pinfunction "2_2") (pintype "passive"))
    )
    (net (code "22") (name "Net-(IC1A-QB)") (class "Default")
      (node (ref "IC1") (pin "1") (pinfunction "QB_1") (pintype "tri_state"))
      (node (ref "R2") (pin "2") (pinfunction "2_2") (pintype "passive"))
    )
    (net (code "23") (name "Net-(IC1A-QC)") (class "Default")
      (node (ref "IC1") (pin "2") (pinfunction "QC_2") (pintype "tri_state"))
      (node (ref "R9") (pin "2") (pinfunction "2_2") (pintype "passive"))
    )
    (net (code "24") (name "Net-(IC1A-QH)") (class "Default")
      (node (ref "IC1") (pin "7") (pinfunction "QH_7") (pintype "tri_state"))
      (node (ref "R35") (pin "2") (pinfunction "2_2") (pintype "passive"))
    )
    (net (code "25") (name "Net-(IC1A-SCL)") (class "Default")
      (node (ref "IC1") (pin "10") (pinfunction "SCL_10") (pintype "input"))
      (node (ref "R44(0)") (pin "1") (pinfunction "1_1") (pintype "passive"))
    )
    (net (code "26") (name "Net-(IC2-VI)") (class "Default")
      (node (ref "C13") (pin "+") (pinfunction "+_+") (pintype "passive"))
      (node (ref "C15") (pin "+") (pinfunction "+_+") (pintype "passive"))
      (node (ref "C5") (pin "2") (pinfunction "2_2") (pintype "passive"))
      (node (ref "IC2") (pin "1") (pinfunction "VI_1") (pintype "input"))
      (node (ref "R13") (pin "1") (pinfunction "1_1") (pintype "passive"))
      (node (ref "R14") (pin "1") (pinfunction "1_1") (pintype "passive"))
      (node (ref "R15") (pin "1") (pinfunction "1_1") (pintype "passive"))
      (node (ref "R17") (pin "1") (pinfunction "1_1") (pintype "passive"))
      (node (ref "R7") (pin "1") (pinfunction "1_1") (pintype "passive"))
    )
    (net (code "27") (name "Net-(IC3-EN)") (class "Default")
      (node (ref "IC3") (pin "5") (pinfunction "EN_5") (pintype "input"))
      (node (ref "R5") (pin "1") (pinfunction "1_1") (pintype "passive"))
    )
    (net (code "28") (name "Net-(IC3-FB)") (class "Default")
      (node (ref "IC3") (pin "4") (pinfunction "FB_4") (pintype "input"))
      (node (ref "R18") (pin "2") (pinfunction "2_2") (pintype "passive"))
      (node (ref "R4") (pin "1") (pinfunction "1_1") (pintype "passive"))
    )
    (net (code "29") (name "Net-(IC3-OUT)") (class "Default")
      (node (ref "D2") (pin "C") (pinfunction "C_C") (pintype "passive"))
      (node (ref "IC3") (pin "2") (pinfunction "OUT_2") (pintype "output"))
      (node (ref "L3") (pin "2") (pinfunction "2_2") (pintype "passive"))
    )
    (net (code "30") (name "Net-(IC4-VIN)") (class "Default")
      (node (ref "IC4") (pin "3") (pinfunction "VIN_3") (pintype "input"))
      (node (ref "R42(0)") (pin "2") (pinfunction "2_2") (pintype "passive"))
      (node (ref "R48(0)") (pin "1") (pinfunction "1_1") (pintype "passive"))
    )
    (net (code "31") (name "Net-(IC5-SCK)") (class "Default")
      (node (ref "IC5") (pin "6") (pinfunction "SCK_6") (pintype "input"))
      (node (ref "R36") (pin "2") (pinfunction "2_2") (pintype "passive"))
    )
    (net (code "32") (name "Net-(IC5-SI)") (class "Default")
      (node (ref "IC5") (pin "5") (pinfunction "SI_5") (pintype "input"))
      (node (ref "R42") (pin "2") (pinfunction "2_2") (pintype "passive"))
    )
    (net (code "33") (name "Net-(IC5-SO)") (class "Default")
      (node (ref "IC5") (pin "2") (pinfunction "SO_2") (pintype "bidirectional"))
      (node (ref "R47") (pin "2") (pinfunction "2_2") (pintype "passive"))
    )
    (net (code "34") (name "Net-(IC5-~{CS})") (class "Default")
      (node (ref "IC5") (pin "1") (pinfunction "~{CS}_1") (pintype "input"))
      (node (ref "R44") (pin "2") (pinfunction "2_2") (pintype "passive"))
    )
    (net (code "35") (name "Net-(IC7-(PCI18{slash}INT0)PD2)") (class "Default")
      (node (ref "IC7") (pin "4") (pinfunction "(PCI18/INT0)PD2_4") (pintype "bidirectional"))
      (node (ref "R1") (pin "1") (pinfunction "1_1") (pintype "passive"))
      (node (ref "SETUP") (pin "1") (pinfunction "S_1") (pintype "passive"))
      (node (ref "SETUP") (pin "2") (pinfunction "S1_2") (pintype "passive"))
    )
    (net (code "36") (name "Net-(IC7-AREF)") (class "Default")
      (node (ref "C2") (pin "2") (pinfunction "2_2") (pintype "passive"))
      (node (ref "IC7") (pin "21") (pinfunction "AREF_21") (pintype "bidirectional"))
    )
    (net (code "37") (name "Net-(IC7-PB6(XTAL1{slash}TOSC1{slash}PCI6))") (class "Default")
      (node (ref "C7") (pin "1") (pinfunction "1_1") (pintype "passive"))
      (node (ref "IC7") (pin "9") (pinfunction "PB6(XTAL1/TOSC1/PCI6)_9") (pintype "bidirectional"))
      (node (ref "Q2") (pin "2") (pinfunction "2_2") (pintype "passive"))
    )
    (net (code "38") (name "Net-(IC7-PB7(XTAL2{slash}TOSC2{slash}PCI7))") (class "Default")
      (node (ref "C9") (pin "1") (pinfunction "1_1") (pintype "passive"))
      (node (ref "IC7") (pin "10") (pinfunction "PB7(XTAL2/TOSC2/PCI7)_10") (pintype "bidirectional"))
      (node (ref "Q2") (pin "1") (pinfunction "1_1") (pintype "passive"))
    )
    (net (code "39") (name "Net-(IC9A-+IN)") (class "Default")
      (node (ref "C23") (pin "1") (pinfunction "1_1") (pintype "passive"))
      (node (ref "IC9") (pin "3") (pinfunction "+IN_3") (pintype "input"))
      (node (ref "R24") (pin "1") (pinfunction "1_1") (pintype "passive"))
      (node (ref "R45") (pin "1") (pinfunction "1_1") (pintype "passive"))
    )
    (net (code "40") (name "Net-(IC9A--IN)") (class "Default")
      (node (ref "C10") (pin "2") (pinfunction "2_2") (pintype "passive"))
      (node (ref "IC9") (pin "2") (pinfunction "-IN_2") (pintype "input"))
      (node (ref "R23") (pin "1") (pinfunction "1_1") (pintype "passive"))
      (node (ref "R38") (pin "2") (pinfunction "2_2") (pintype "passive"))
    )
    (net (code "41") (name "Net-(IC10-VBAT)") (class "Default")
      (node (ref "BAT") (pin "+") (pinfunction "+_+") (pintype "bidirectional"))
      (node (ref "IC10") (pin "3") (pinfunction "VBAT_3") (pintype "power_in"))
    )
    (net (code "42") (name "Net-(IC10-X1)") (class "Default")
      (node (ref "IC10") (pin "1") (pinfunction "X1_1") (pintype "passive"))
      (node (ref "Q4") (pin "2") (pinfunction "2_2") (pintype "passive"))
    )
    (net (code "43") (name "Net-(IC10-X2)") (class "Default")
      (node (ref "IC10") (pin "2") (pinfunction "X2_2") (pintype "passive"))
      (node (ref "Q4") (pin "1") (pinfunction "1_1") (pintype "passive"))
    )
    (net (code "44") (name "Net-(IC12-A)") (class "Default")
      (node (ref "IC12") (pin "6") (pinfunction "A_6") (pintype "bidirectional"))
      (node (ref "R11") (pin "2") (pinfunction "2_2") (pintype "passive"))
      (node (ref "R30") (pin "2") (pinfunction "2_2") (pintype "passive"))
      (node (ref "X8") (pin "2") (pinfunction "2_2") (pintype "passive"))
    )
    (net (code "45") (name "Net-(IC12-B)") (class "Default")
      (node (ref "IC12") (pin "7") (pinfunction "B_7") (pintype "bidirectional"))
      (node (ref "R10") (pin "1") (pinfunction "1_1") (pintype "passive"))
      (node (ref "R30") (pin "1") (pinfunction "1_1") (pintype "passive"))
      (node (ref "X8") (pin "1") (pinfunction "1_1") (pintype "passive"))
    )
    (net (code "46") (name "Net-(J14-Pad2)") (class "Default")
      (node (ref "J14") (pin "2") (pinfunction "2_2") (pintype "passive"))
      (node (ref "R39") (pin "2") (pinfunction "2_2") (pintype "passive"))
    )
    (net (code "47") (name "Net-(J14-Pad3)") (class "Default")
      (node (ref "J14") (pin "3") (pinfunction "3_3") (pintype "passive"))
      (node (ref "R40") (pin "2") (pinfunction "2_2") (pintype "passive"))
    )
    (net (code "48") (name "Net-(J14-Pad4)") (class "Default")
      (node (ref "J14") (pin "4") (pinfunction "4_4") (pintype "passive"))
      (node (ref "R41") (pin "2") (pinfunction "2_2") (pintype "passive"))
    )
    (net (code "49") (name "Net-(LIVE-PadA)") (class "Default")
      (node (ref "LIVE") (pin "A") (pinfunction "A_A") (pintype "passive"))
      (node (ref "R2") (pin "1") (pinfunction "1_1") (pintype "passive"))
    )
    (net (code "50") (name "Net-(NET-PadA)") (class "Default")
      (node (ref "NET") (pin "A") (pinfunction "A_A") (pintype "passive"))
      (node (ref "R9") (pin "1") (pinfunction "1_1") (pintype "passive"))
    )
    (net (code "51") (name "Net-(POW-PadA)") (class "Default")
      (node (ref "POW") (pin "A") (pinfunction "A_A") (pintype "passive"))
      (node (ref "R12") (pin "1") (pinfunction "1_1") (pintype "passive"))
    )
    (net (code "52") (name "Net-(Q3-D)") (class "Default")
      (node (ref "JCS") (pin "1") (pinfunction "1_1") (pintype "passive"))
      (node (ref "Q3") (pin "1") (pinfunction "D_1") (pintype "passive"))
      (node (ref "R19") (pin "1") (pinfunction "1_1") (pintype "passive"))
      (node (ref "R44") (pin "1") (pinfunction "1_1") (pintype "passive"))
      (node (ref "SD2") (pin "2") (pinfunction "CD/DAT3(~{CS})_2") (pintype "bidirectional"))
    )
    (net (code "53") (name "Net-(Q3-G)") (class "Default")
      (node (ref "Q3") (pin "2") (pinfunction "G_2") (pintype "passive"))
      (node (ref "Q5") (pin "2") (pinfunction "G_2") (pintype "passive"))
      (node (ref "Q6") (pin "2") (pinfunction "G_2") (pintype "passive"))
      (node (ref "R42(0)") (pin "1") (pinfunction "1_1") (pintype "passive"))
    )
    (net (code "54") (name "Net-(Q5-D)") (class "Default")
      (node (ref "JSCK") (pin "1") (pinfunction "1_1") (pintype "passive"))
      (node (ref "Q5") (pin "1") (pinfunction "D_1") (pintype "passive"))
      (node (ref "R21") (pin "1") (pinfunction "1_1") (pintype "passive"))
      (node (ref "R36") (pin "1") (pinfunction "1_1") (pintype "passive"))
      (node (ref "SD2") (pin "5") (pinfunction "CLK(SCLK)_5") (pintype "input"))
    )
    (net (code "55") (name "Net-(Q6-D)") (class "Default")
      (node (ref "JMOSI") (pin "1") (pinfunction "1_1") (pintype "passive"))
      (node (ref "Q6") (pin "1") (pinfunction "D_1") (pintype "passive"))
      (node (ref "R22") (pin "1") (pinfunction "1_1") (pintype "passive"))
      (node (ref "R42") (pin "1") (pinfunction "1_1") (pintype "passive"))
      (node (ref "SD2") (pin "3") (pinfunction "CMD(DI)_3") (pintype "bidirectional"))
    )
    (net (code "56") (name "Net-(R8-Pad1)") (class "Default")
      (node (ref "R8") (pin "1") (pinfunction "1_1") (pintype "passive"))
      (node (ref "T5") (pin "B") (pinfunction "B_B") (pintype "passive"))
    )
    (net (code "57") (name "Net-(R25-Pad1)") (class "Default")
      (node (ref "R25") (pin "1") (pinfunction "1_1") (pintype "passive"))
      (node (ref "R26") (pin "2") (pinfunction "2_2") (pintype "passive"))
      (node (ref "R37") (pin "2") (pinfunction "2_2") (pintype "passive"))
      (node (ref "R51") (pin "1") (pinfunction "1_1") (pintype "passive"))
      (node (ref "R52") (pin "1") (pinfunction "1_1") (pintype "passive"))
      (node (ref "R53") (pin "1") (pinfunction "1_1") (pintype "passive"))
      (node (ref "R54") (pin "2") (pinfunction "2_2") (pintype "passive"))
      (node (ref "R55") (pin "2") (pinfunction "2_2") (pintype "passive"))
      (node (ref "R56") (pin "2") (pinfunction "2_2") (pintype "passive"))
    )
    (net (code "58") (name "Net-(R35-Pad1)") (class "Default")
      (node (ref "R35") (pin "1") (pinfunction "1_1") (pintype "passive"))
      (node (ref "R8") (pin "2") (pinfunction "2_2") (pintype "passive"))
    )
    (net (code "59") (name "Net-(SD2-DAT0(DO))") (class "Default")
      (node (ref "JMISO") (pin "1") (pinfunction "1_1") (pintype "passive"))
      (node (ref "R43") (pin "1") (pinfunction "1_1") (pintype "passive"))
      (node (ref "R47") (pin "1") (pinfunction "1_1") (pintype "passive"))
      (node (ref "R59") (pin "1") (pinfunction "1_1") (pintype "passive"))
      (node (ref "R59") (pin "2") (pinfunction "2_2") (pintype "passive"))
      (node (ref "SD2") (pin "7") (pinfunction "DAT0(DO)_7") (pintype "bidirectional"))
    )
    (net (code "60") (name "Net-(X1A-KL)") (class "Default")
      (node (ref "D1") (pin "A") (pinfunction "A_A") (pintype "passive"))
      (node (ref "J2") (pin "2") (pinfunction "2_2") (pintype "passive"))
      (node (ref "X1") (pin "1") (pinfunction "KL_1") (pintype "passive"))
    )
    (net (code "61") (name "Net-(X1D-KL)") (class "Default")
      (node (ref "J2") (pin "1") (pinfunction "1_1") (pintype "passive"))
      (node (ref "R25") (pin "2") (pinfunction "2_2") (pintype "passive"))
      (node (ref "R51") (pin "2") (pinfunction "2_2") (pintype "passive"))
      (node (ref "R52") (pin "2") (pinfunction "2_2") (pintype "passive"))
      (node (ref "R53") (pin "2") (pinfunction "2_2") (pintype "passive"))
      (node (ref "X1") (pin "3") (pinfunction "KL_3") (pintype "passive"))
    )
    (net (code "62") (name "Net-(X8-Pad4)") (class "Default")
      (node (ref "X8") (pin "4") (pinfunction "4_4") (pintype "passive"))
      (node (ref "X8") (pin "5") (pinfunction "5_5") (pintype "passive"))
    )
    (net (code "63") (name "RCK") (class "Default")
      (node (ref "IC1") (pin "12") (pinfunction "RCK_12") (pintype "input"))
      (node (ref "IC7") (pin "12") (pinfunction "(PCI22/AIN0OC0A)PD6_12") (pintype "bidirectional"))
    )
    (net (code "64") (name "RELAY_485") (class "Default")
      (node (ref "IC1") (pin "3") (pinfunction "QD_3") (pintype "tri_state"))
      (node (ref "R16") (pin "1") (pinfunction "1_1") (pintype "passive"))
    )
    (net (code "65") (name "RST") (class "Default")
      (node (ref "IC7") (pin "1") (pinfunction "PC6(/RESET/PCI14)_1") (pintype "bidirectional"))
      (node (ref "JP2") (pin "1") (pinfunction "1_1") (pintype "passive"))
      (node (ref "JP2") (pin "2") (pinfunction "2_2") (pintype "passive"))
      (node (ref "JP8") (pin "5") (pinfunction "5_5") (pintype "passive"))
      (node (ref "R6") (pin "1") (pinfunction "1_1") (pintype "passive"))
    )
    (net (code "66") (name "RX1") (class "Default")
      (node (ref "IC12") (pin "1") (pinfunction "RO_1") (pintype "output"))
      (node (ref "IC7") (pin "15") (pinfunction "(PCI1/OC1A/OC1S)PB1_15") (pintype "bidirectional"))
      (node (ref "R3") (pin "2") (pinfunction "2_2") (pintype "passive"))
    )
    (net (code "67") (name "RX2") (class "Default")
      (node (ref "IC7") (pin "5") (pinfunction "(PCI19/INT1/OC2B)PD3_5") (pintype "bidirectional"))
      (node (ref "R41") (pin "1") (pinfunction "1_1") (pintype "passive"))
    )
    (net (code "68") (name "RXD") (class "Default")
      (node (ref "IC7") (pin "2") (pinfunction "(PCI16/RXD)PD0_2") (pintype "bidirectional"))
      (node (ref "JP2") (pin "4") (pinfunction "4_4") (pintype "passive"))
      (node (ref "JP8") (pin "2") (pinfunction "2_2") (pintype "passive"))
    )
    (net (code "69") (name "SCK") (class "Default")
      (node (ref "IC7") (pin "19") (pinfunction "(PCI5/SCK)PB5_19") (pintype "bidirectional"))
      (node (ref "J8") (pin "3") (pinfunction "3_3") (pintype "passive"))
      (node (ref "Q5") (pin "3") (pinfunction "S_3") (pintype "passive"))
      (node (ref "R58") (pin "1") (pinfunction "1_1") (pintype "passive"))
      (node (ref "R58") (pin "2") (pinfunction "2_2") (pintype "passive"))
    )
    (net (code "70") (name "SCK2") (class "Default")
      (node (ref "IC1") (pin "11") (pinfunction "SCK_11") (pintype "input"))
      (node (ref "IC7") (pin "11") (pinfunction "(PCI21/T1/OC0B)PD5_11") (pintype "bidirectional"))
    )
    (net (code "71") (name "SCL") (class "Default")
      (node (ref "IC10") (pin "6") (pinfunction "SCL_6") (pintype "bidirectional"))
      (node (ref "IC7") (pin "28") (pinfunction "(PCI13/ADC5/SCL)PC5_28") (pintype "bidirectional"))
      (node (ref "R28") (pin "2") (pinfunction "2_2") (pintype "passive"))
    )
    (net (code "72") (name "SDA") (class "Default")
      (node (ref "IC10") (pin "5") (pinfunction "SDA_5") (pintype "bidirectional"))
      (node (ref "IC7") (pin "27") (pinfunction "(PCI12/ADC4/SDA)PC4_27") (pintype "bidirectional"))
      (node (ref "R29") (pin "1") (pinfunction "1_1") (pintype "passive"))
    )
    (net (code "73") (name "SD_CS") (class "Default")
      (node (ref "IC7") (pin "16") (pinfunction "(PCI2/SS/OC1B)PB2_16") (pintype "bidirectional"))
      (node (ref "Q3") (pin "3") (pinfunction "S_3") (pintype "passive"))
      (node (ref "R48") (pin "1") (pinfunction "1_1") (pintype "passive"))
      (node (ref "R48") (pin "2") (pinfunction "2_2") (pintype "passive"))
    )
    (net (code "74") (name "SER") (class "Default")
      (node (ref "IC1") (pin "14") (pinfunction "SER_14") (pintype "input"))
      (node (ref "IC7") (pin "13") (pinfunction "(PCI23/AIN1)PD7_13") (pintype "bidirectional"))
    )
    (net (code "75") (name "SIM_POW") (class "Default")
      (node (ref "C20") (pin "+") (pinfunction "+_+") (pintype "passive"))
      (node (ref "C22") (pin "1") (pinfunction "1_1") (pintype "passive"))
      (node (ref "C25") (pin "+") (pinfunction "+_+") (pintype "passive"))
      (node (ref "C8") (pin "+") (pinfunction "+_+") (pintype "passive"))
      (node (ref "D4") (pin "C") (pinfunction "C_C") (pintype "passive"))
      (node (ref "J14") (pin "1") (pinfunction "1_1") (pintype "passive"))
      (node (ref "JP1") (pin "1") (pinfunction "1_1") (pintype "passive"))
      (node (ref "JP3") (pin "1") (pinfunction "1_1") (pintype "passive"))
      (node (ref "L3") (pin "1") (pinfunction "1_1") (pintype "passive"))
      (node (ref "R4") (pin "2") (pinfunction "2_2") (pintype "passive"))
    )
    (net (code "76") (name "SQW") (class "Default")
      (node (ref "IC10") (pin "7") (pinfunction "SQW/OUT_7") (pintype "bidirectional"))
    )
    (net (code "77") (name "TX1") (class "Default")
      (node (ref "IC12") (pin "4") (pinfunction "DI_4") (pintype "input"))
      (node (ref "IC7") (pin "14") (pinfunction "(PCI0/ICP/CLKO)PB0_14") (pintype "bidirectional"))
      (node (ref "R20") (pin "2") (pinfunction "2_2") (pintype "passive"))
    )
    (net (code "78") (name "TX2") (class "Default")
      (node (ref "IC7") (pin "6") (pinfunction "(PCI20/XCK/T0)PD4_6") (pintype "bidirectional"))
      (node (ref "R40") (pin "1") (pinfunction "1_1") (pintype "passive"))
    )
    (net (code "79") (name "TXD") (class "Default")
      (node (ref "IC7") (pin "3") (pinfunction "(PCI17/TXD)PD1_3") (pintype "bidirectional"))
      (node (ref "JP2") (pin "6") (pinfunction "6_6") (pintype "passive"))
      (node (ref "JP8") (pin "1") (pinfunction "1_1") (pintype "passive"))
    )
    (net (code "80") (name "VCC") (class "Default")
      (node (ref "BUZ") (pin "+") (pinfunction "+_+") (pintype "passive"))
      (node (ref "C12") (pin "2") (pinfunction "2_2") (pintype "passive"))
      (node (ref "C14") (pin "2") (pinfunction "2_2") (pintype "passive"))
      (node (ref "C16") (pin "2") (pinfunction "2_2") (pintype "passive"))
      (node (ref "C18") (pin "+") (pinfunction "+_+") (pintype "passive"))
      (node (ref "C21") (pin "2") (pinfunction "2_2") (pintype "passive"))
      (node (ref "C3") (pin "+") (pinfunction "+_+") (pintype "passive"))
      (node (ref "C30") (pin "2") (pinfunction "2_2") (pintype "passive"))
      (node (ref "C31") (pin "+") (pinfunction "+_+") (pintype "passive"))
      (node (ref "C36") (pin "2") (pinfunction "2_2") (pintype "passive"))
      (node (ref "C6") (pin "2") (pinfunction "2_2") (pintype "passive"))
      (node (ref "D6") (pin "A") (pinfunction "A_A") (pintype "passive"))
      (node (ref "IC1") (pin "16") (pinfunction "VCC_16") (pintype "power_in"))
      (node (ref "IC10") (pin "8") (pinfunction "VCC_8") (pintype "power_in"))
      (node (ref "IC12") (pin "8") (pinfunction "VCC_8") (pintype "input"))
      (node (ref "IC2") (pin "3") (pinfunction "VO_3") (pintype "passive"))
      (node (ref "IC7") (pin "7") (pinfunction "VCC_7") (pintype "bidirectional"))
      (node (ref "IC9") (pin "8") (pinfunction "V+_8") (pintype "power_in"))
      (node (ref "JP1") (pin "8") (pinfunction "8_8") (pintype "passive"))
      (node (ref "JP2") (pin "3") (pinfunction "3_3") (pintype "passive"))
      (node (ref "JP3") (pin "8") (pinfunction "8_8") (pintype "passive"))
      (node (ref "JP6") (pin "6") (pinfunction "6_6") (pintype "passive"))
      (node (ref "JP7") (pin "6") (pinfunction "6_6") (pintype "passive"))
      (node (ref "JP8") (pin "4") (pinfunction "4_4") (pintype "passive"))
      (node (ref "L1") (pin "1") (pinfunction "1_1") (pintype "passive"))
      (node (ref "R10") (pin "2") (pinfunction "2_2") (pintype "passive"))
      (node (ref "R12") (pin "2") (pinfunction "2_2") (pintype "passive"))
      (node (ref "R20") (pin "1") (pinfunction "1_1") (pintype "passive"))
      (node (ref "R28") (pin "1") (pinfunction "1_1") (pintype "passive"))
      (node (ref "R29") (pin "2") (pinfunction "2_2") (pintype "passive"))
      (node (ref "R3") (pin "1") (pinfunction "1_1") (pintype "passive"))
      (node (ref "R32") (pin "1") (pinfunction "1_1") (pintype "passive"))
      (node (ref "R34") (pin "1") (pinfunction "1_1") (pintype "passive"))
      (node (ref "R44(0)") (pin "2") (pinfunction "2_2") (pintype "passive"))
      (node (ref "R46") (pin "1") (pinfunction "1_1") (pintype "passive"))
      (node (ref "R48(0)") (pin "2") (pinfunction "2_2") (pintype "passive"))
      (node (ref "R6") (pin "2") (pinfunction "2_2") (pintype "passive"))
      (node (ref "SETUP") (pin "3") (pinfunction "P_3") (pintype "passive"))
      (node (ref "SETUP") (pin "4") (pinfunction "P1_4") (pintype "passive"))
    )
    (net (code "81") (name "unconnected-(IC1A-QH*-Pad9)") (class "Default")
      (node (ref "IC1") (pin "9") (pinfunction "QH*_9") (pintype "tri_state"))
    )
    (net (code "82") (name "unconnected-(JP1-Pad6)") (class "Default")
      (node (ref "JP1") (pin "6") (pinfunction "6_6") (pintype "passive"))
    )
    (net (code "83") (name "unconnected-(JP3-Pad6)") (class "Default")
      (node (ref "JP3") (pin "6") (pinfunction "6_6") (pintype "passive"))
    )
    (net (code "84") (name "unconnected-(R16-Pad2)") (class "Default")
      (node (ref "R16") (pin "2") (pinfunction "2_2") (pintype "passive"))
    )
    (net (code "85") (name "unconnected-(SD2-DAT1-Pad8)") (class "Default")
      (node (ref "SD2") (pin "8") (pinfunction "DAT1_8") (pintype "bidirectional"))
    )
    (net (code "86") (name "unconnected-(SD2-DAT2-Pad1)") (class "Default")
      (node (ref "SD2") (pin "1") (pinfunction "DAT2_1") (pintype "bidirectional"))
    )
    (net (code "87") (name "unconnected-(SD2-~{CARD}-Pad9)") (class "Default")
      (node (ref "SD2") (pin "9") (pinfunction "~{CARD}_9") (pintype "passive"))
    )
    (net (code "88") (name "unconnected-(U$1-PadDTR)") (class "Default")
      (node (ref "U$1") (pin "DTR") (pinfunction "DTR_DTR") (pintype "bidirectional"))
    )
    (net (code "89") (name "unconnected-(U$1-PadGND)") (class "Default")
      (node (ref "U$1") (pin "GND") (pinfunction "GND_GND") (pintype "bidirectional"))
    )
    (net (code "90") (name "unconnected-(U$1-PadMIC+)") (class "Default")
      (node (ref "U$1") (pin "MIC+") (pinfunction "MIC+_MIC+") (pintype "bidirectional"))
    )
    (net (code "91") (name "unconnected-(U$1-PadMIC-)") (class "Default")
      (node (ref "U$1") (pin "MIC-") (pinfunction "MIC-_MIC-") (pintype "bidirectional"))
    )
    (net (code "92") (name "unconnected-(U$1-PadNET)") (class "Default")
      (node (ref "U$1") (pin "NET") (pinfunction "NET_NET") (pintype "bidirectional"))
    )
    (net (code "93") (name "unconnected-(U$1-PadRING)") (class "Default")
      (node (ref "U$1") (pin "RING") (pinfunction "RING_RING") (pintype "bidirectional"))
    )
    (net (code "94") (name "unconnected-(U$1-PadRST)") (class "Default")
      (node (ref "U$1") (pin "RST") (pinfunction "RST_RST") (pintype "bidirectional"))
    )
    (net (code "95") (name "unconnected-(U$1-PadRX)") (class "Default")
      (node (ref "U$1") (pin "RX") (pinfunction "RX_RX") (pintype "bidirectional"))
    )
    (net (code "96") (name "unconnected-(U$1-PadSPK+)") (class "Default")
      (node (ref "U$1") (pin "SPK+") (pinfunction "SPK+_SPK+") (pintype "bidirectional"))
    )
    (net (code "97") (name "unconnected-(U$1-PadSPK-)") (class "Default")
      (node (ref "U$1") (pin "SPK-") (pinfunction "SPK-_SPK-") (pintype "bidirectional"))
    )
    (net (code "98") (name "unconnected-(U$1-PadTX)") (class "Default")
      (node (ref "U$1") (pin "TX") (pinfunction "TX_TX") (pintype "bidirectional"))
    )
    (net (code "99") (name "unconnected-(U$1-PadVCC)") (class "Default")
      (node (ref "U$1") (pin "VCC") (pinfunction "VCC_VCC") (pintype "bidirectional"))
    )
  )
)
